# CAS_5.net
KiCad netlist of a schematic drawn in Altium Designer
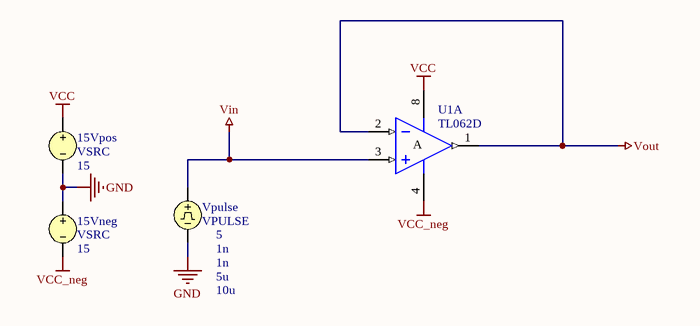
[diagram p0: CAS_5.SchDoc]

(export (version "E")
  (design (tool "Eeschema 10.0.6"))
  (components
    (comp (ref "15Vneg")
      (value "VSRC")
      (description "Voltage Source")
      (fields (field (name "ALTIUM_VALUE") "15") (field (name "PUBLISHER") "Altium Limited"))
      (libsource (lib "Simulation Generic Components") (part "VSRC"))
    )
    (comp (ref "15Vpos")
      (value "VSRC")
      (description "Voltage Source")
      (fields (field (name "ALTIUM_VALUE") "15") (field (name "PUBLISHER") "Altium Limited"))
      (libsource (lib "Simulation Generic Components") (part "VSRC"))
    )
    (comp (ref "U1")
      (value "TL062D")
      (footprint "D008_L")
      (description "Low-Power JFET-Input Operational Amplifier")
      (fields (field (name "PUBLISHER") "Altium Limited"))
      (libsource (lib "TI Operational Amplifier") (part "TL062D"))
    )
    (comp (ref "Vpulse")
      (value "VPULSE")
      (description "Pulse Voltage Source")
      (fields
        (field (name "PULSED VALUE") "5")
        (field (name "RISE TIME") "1n")
        (field (name "FALL TIME") "1n")
        (field (name "PULSE WIDTH") "5u")
        (field (name "PERIOD") "10u")
        (field (name "PUBLISHER") "Altium Limited")
      )
      (libsource (lib "Simulation Sources") (part "VPULSE"))
    )
  )
  (nets
    (net (code "1") (name "GND") (class "Default")
      (node (ref "15Vneg") (pin "1") (pinfunction "1_1") (pintype "passive"))
      (node (ref "15Vpos") (pin "2") (pinfunction "2_2") (pintype "passive"))
      (node (ref "Vpulse") (pin "2") (pinfunction "2_2") (pintype "passive"))
    )
    (net (code "2") (name "VCC") (class "Default")
      (node (ref "15Vpos") (pin "1") (pinfunction "1_1") (pintype "passive"))
      (node (ref "U1") (pin "8") (pinfunction "V+_8") (pintype "power_in"))
    )
    (net (code "3") (name "VCC_neg") (class "Default")
      (node (ref "15Vneg") (pin "2") (pinfunction "2_2") (pintype "passive"))
      (node (ref "U1") (pin "4") (pinfunction "V-_4") (pintype "power_in"))
    )
    (net (code "4") (name "Vin") (class "Default")
      (node (ref "U1") (pin "3") (pinfunction "IN+_3") (pintype "input"))
      (node (ref "Vpulse") (pin "1") (pinfunction "1_1") (pintype "passive"))
    )
    (net (code "5") (name "Vout") (class "Default")
      (node (ref "U1") (pin "1") (pinfunction "OUT_1") (pintype "output"))
      (node (ref "U1") (pin "2") (pinfunction "IN-_2") (pintype "input"))
    )
  )
)
